# other.net
KiCad netlist of a schematic drawn in Altium Designer
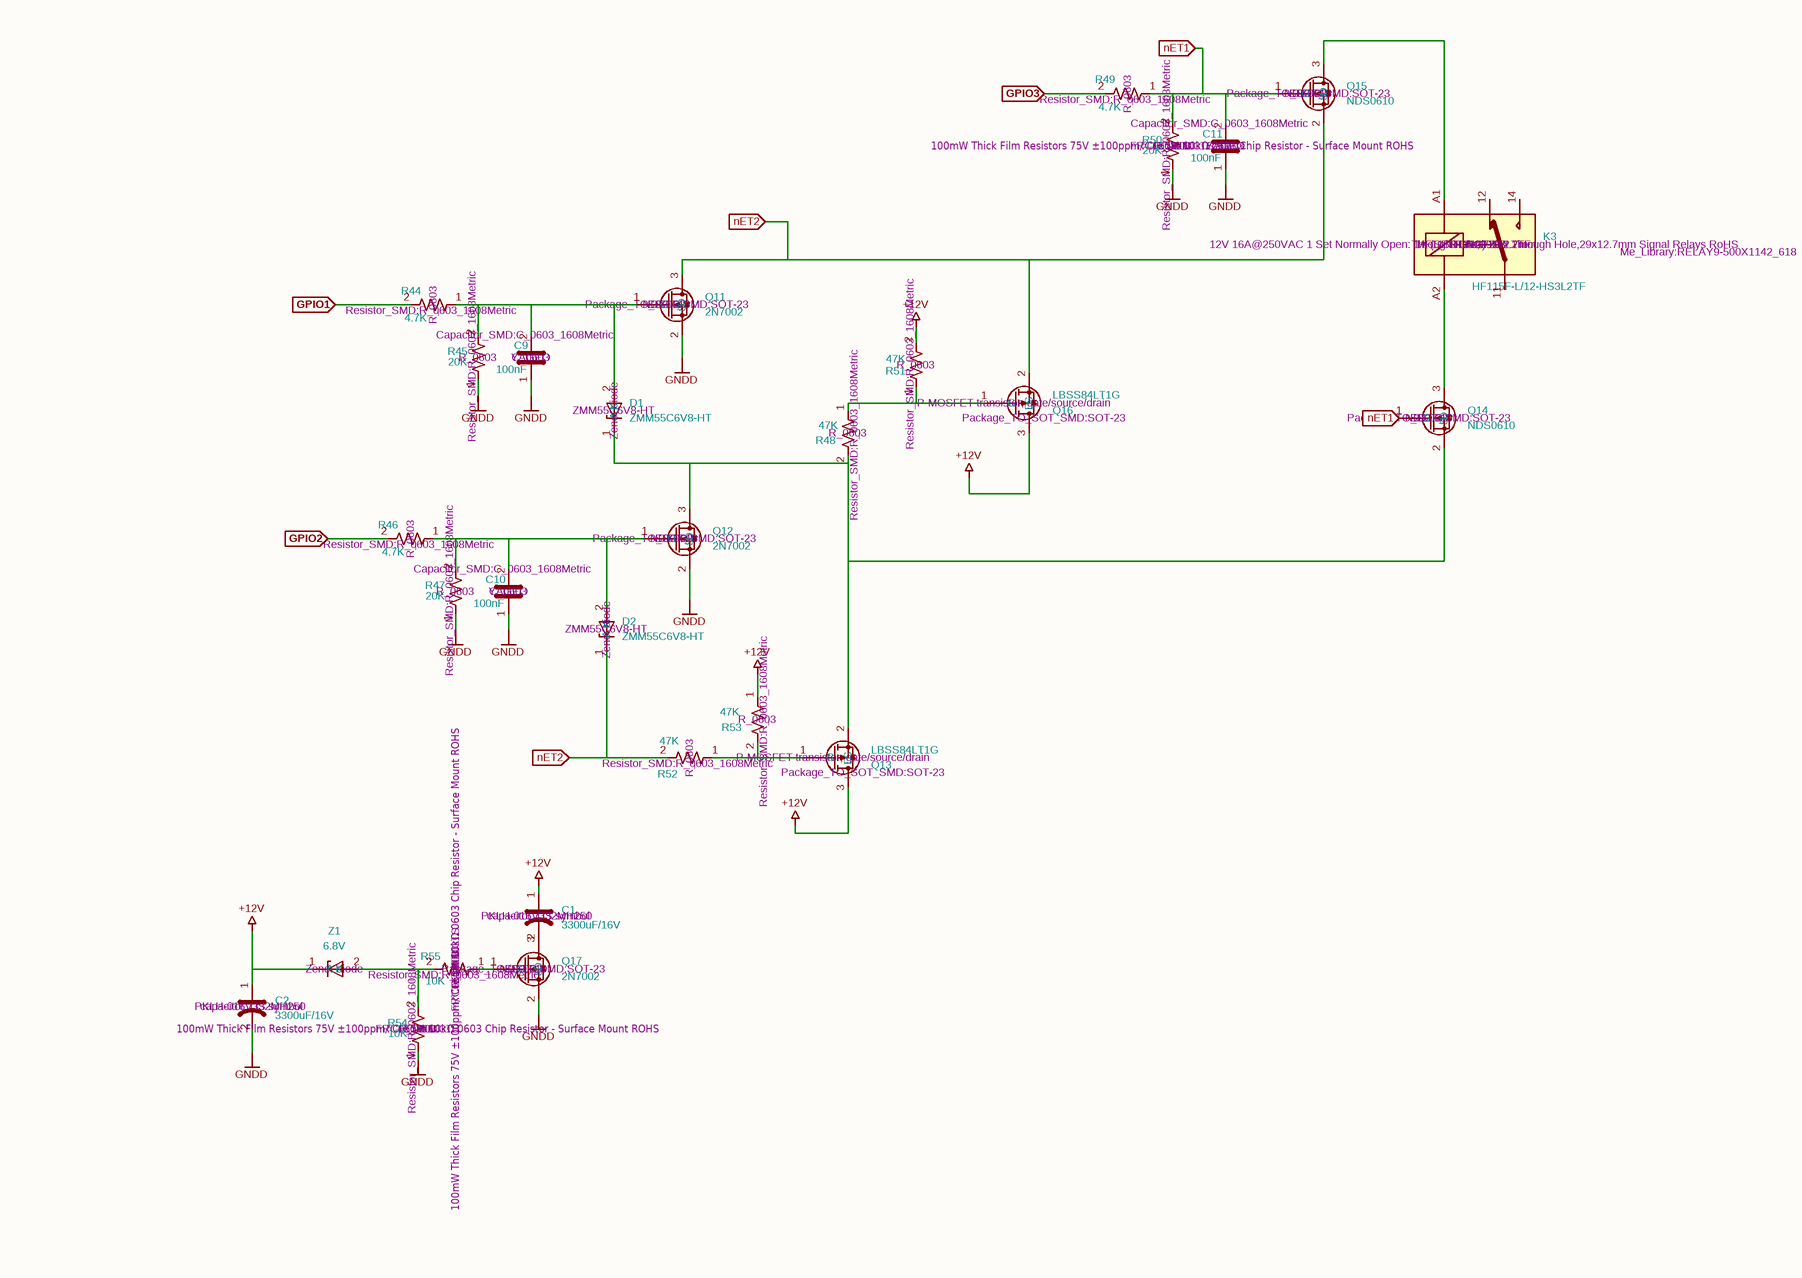
[diagram p0: other.SchDoc, left]
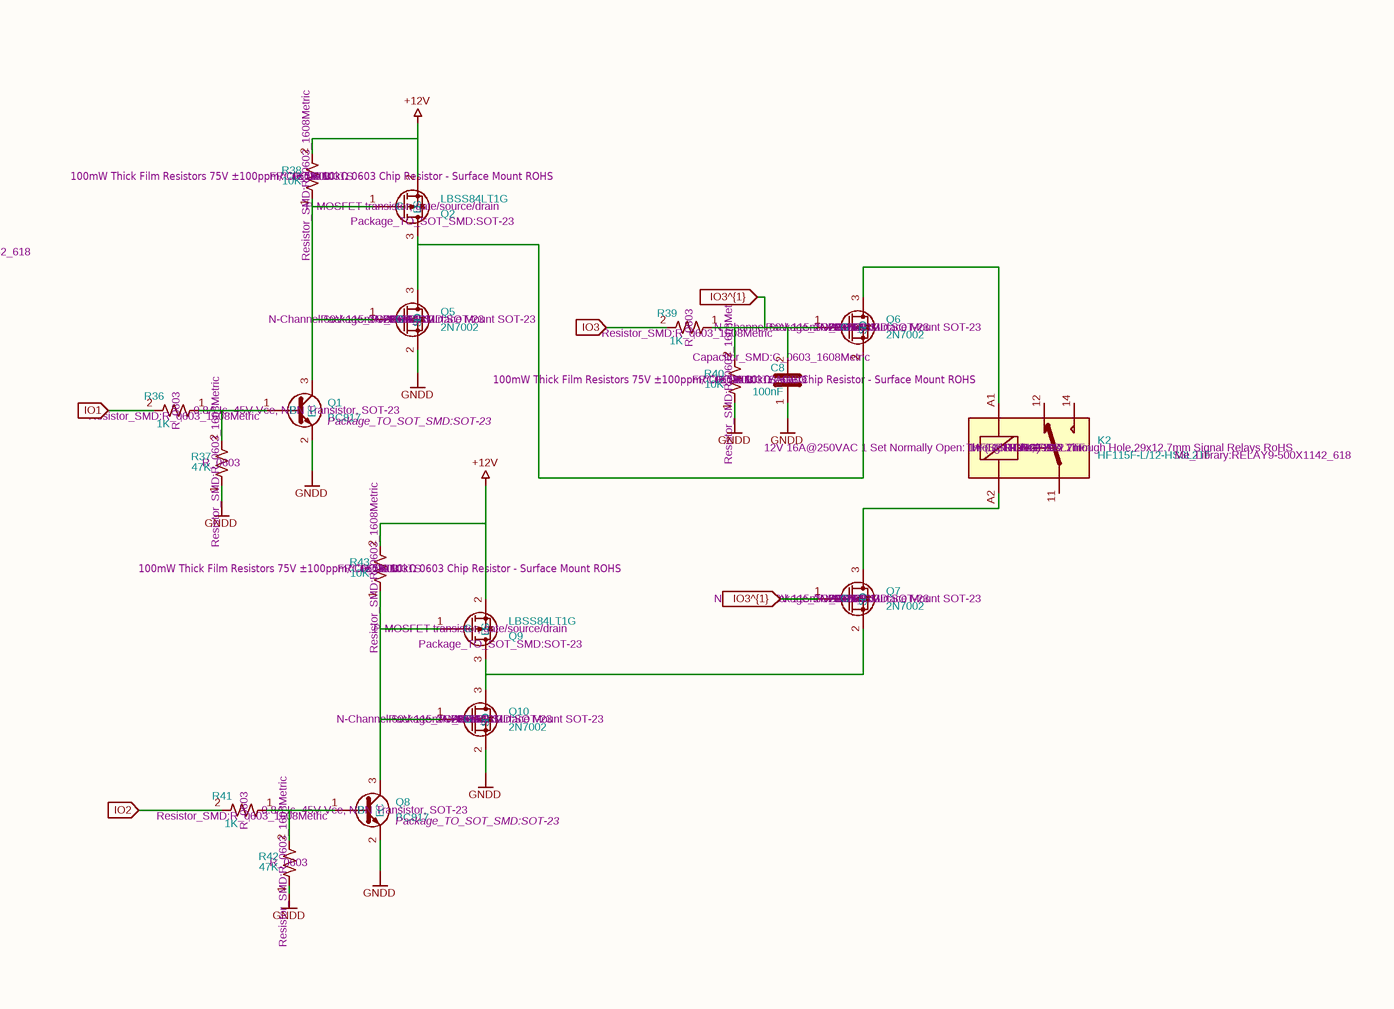
[diagram p1: other.SchDoc, right]

(export (version "E")
  (design (tool "Eeschema 10.0.6"))
  (components
    (comp (ref "C1")
      (value "3300uF/16V")
      (description "capacitor, US symbol")
      (fields (field (name "OZD") "PKLH-016V332MH250"))
      (libsource (lib "Device") (part "C_US"))
    )
    (comp (ref "C2")
      (value "3300uF/16V")
      (description "capacitor, US symbol")
      (fields (field (name "OZD") "PKLH-016V332MH250"))
      (libsource (lib "Device") (part "C_US"))
    )
    (comp (ref "C8")
      (value "100nF")
      (footprint "Capacitor_SMD:C_0603_1608Metric")
      (fields (field (name "MF") "YAGEO") (field (name "PACKAGE") "C_0603"))
      (libsource (lib "*") (part "C_3"))
    )
    (comp (ref "C9")
      (value "100nF")
      (footprint "Capacitor_SMD:C_0603_1608Metric")
      (fields (field (name "MF") "YAGEO") (field (name "PACKAGE") "C_0603"))
      (libsource (lib "*") (part "C_3"))
    )
    (comp (ref "C10")
      (value "100nF")
      (footprint "Capacitor_SMD:C_0603_1608Metric")
      (fields (field (name "MF") "YAGEO") (field (name "PACKAGE") "C_0603"))
      (libsource (lib "*") (part "C_3"))
    )
    (comp (ref "C11")
      (value "100nF")
      (footprint "Capacitor_SMD:C_0603_1608Metric")
      (fields (field (name "MF") "YAGEO") (field (name "PACKAGE") "C_0603"))
      (libsource (lib "*") (part "C_3"))
    )
    (comp (ref "D1")
      (value "ZMM55C6V8-HT")
      (description "Zener diode")
      (fields (field (name "OZD") "ZMM55C6V8-HT"))
      (libsource (lib "*") (part "D_Zener_1"))
    )
    (comp (ref "D2")
      (value "ZMM55C6V8-HT")
      (description "Zener diode")
      (fields (field (name "OZD") "ZMM55C6V8-HT"))
      (libsource (lib "Device") (part "D_Zener"))
    )
    (comp (ref "K2")
      (value "HF115F-L/12-HS3L2TF")
      (footprint "Me_Library:RELAY9-500X1142_618")
      (description "12V 16A@250VAC 1 Set Normally Open: 1A (SPST NO) 20A Through Hole,29x12.7mm Signal Relays RoHS")
      (fields
        (field (name "MP") "HF115F-L/12-HS3L2TF")
        (field (name "MF") "HONGFA")
        (field (name "PACKAGE") "Through Hole,29x12.7mm")
        (field (name "OZD") "RT314F12")
      )
      (libsource (lib "*") (part "RT314A03_1"))
    )
    (comp (ref "K3")
      (value "HF115F-L/12-HS3L2TF")
      (footprint "Me_Library:RELAY9-500X1142_618")
      (description "12V 16A@250VAC 1 Set Normally Open: 1A (SPST NO) 20A Through Hole,29x12.7mm Signal Relays RoHS")
      (fields
        (field (name "MP") "HF115F-L/12-HS3L2TF")
        (field (name "MF") "HONGFA")
        (field (name "PACKAGE") "Through Hole,29x12.7mm")
        (field (name "OZD") "RT314F12")
      )
      (libsource (lib "*") (part "RT314A03_1"))
    )
    (comp (ref "Q1")
      (value "BC817")
      (footprint "Package_TO_SOT_SMD:SOT-23")
      (description "0.8A Ic, 45V Vce, NPN Transistor, SOT-23")
      (libsource (lib "Transistor_BJT") (part "BC817"))
    )
    (comp (ref "Q2")
      (value "LBSS84LT1G")
      (footprint "Package_TO_SOT_SMD:SOT-23")
      (description "P-MOSFET transistor, gate/source/drain")
      (libsource (lib "Transistor_FET") (part "Q_PMOS_GSD"))
    )
    (comp (ref "Q5")
      (value "2N7002")
      (footprint "Package_TO_SOT_SMD:SOT-23")
      (description "N-Channel 60V 115mA 225mW Surface Mount SOT-23")
      (fields
        (field (name "MP") "2N7002")
        (field (name "MF") "FOSAN")
        (field (name "PACKAGE") "SOT-23")
        (field (name "OZD") "2N7002ET1G")
      )
      (libsource (lib "Transistor_FET_Other") (part "Q_NMOS_Depletion_GSD"))
    )
    (comp (ref "Q6")
      (value "2N7002")
      (footprint "Package_TO_SOT_SMD:SOT-23")
      (description "N-Channel 60V 115mA 225mW Surface Mount SOT-23")
      (fields
        (field (name "MP") "2N7002")
        (field (name "MF") "FOSAN")
        (field (name "PACKAGE") "SOT-23")
        (field (name "OZD") "2N7002ET1G")
      )
      (libsource (lib "Transistor_FET_Other") (part "Q_NMOS_Depletion_GSD"))
    )
    (comp (ref "Q7")
      (value "2N7002")
      (footprint "Package_TO_SOT_SMD:SOT-23")
      (description "N-Channel 60V 115mA 225mW Surface Mount SOT-23")
      (fields
        (field (name "MP") "2N7002")
        (field (name "MF") "FOSAN")
        (field (name "PACKAGE") "SOT-23")
        (field (name "OZD") "2N7002ET1G")
      )
      (libsource (lib "Transistor_FET_Other") (part "Q_NMOS_Depletion_GSD"))
    )
    (comp (ref "Q8")
      (value "BC817")
      (footprint "Package_TO_SOT_SMD:SOT-23")
      (description "0.8A Ic, 45V Vce, NPN Transistor, SOT-23")
      (libsource (lib "Transistor_BJT") (part "BC817"))
    )
    (comp (ref "Q9")
      (value "LBSS84LT1G")
      (footprint "Package_TO_SOT_SMD:SOT-23")
      (description "P-MOSFET transistor, gate/source/drain")
      (libsource (lib "Transistor_FET") (part "Q_PMOS_GSD"))
    )
    (comp (ref "Q10")
      (value "2N7002")
      (footprint "Package_TO_SOT_SMD:SOT-23")
      (description "N-Channel 60V 115mA 225mW Surface Mount SOT-23")
      (fields
        (field (name "MP") "2N7002")
        (field (name "MF") "FOSAN")
        (field (name "PACKAGE") "SOT-23")
        (field (name "OZD") "2N7002ET1G")
      )
      (libsource (lib "Transistor_FET_Other") (part "Q_NMOS_Depletion_GSD"))
    )
    (comp (ref "Q11")
      (value "2N7002")
      (footprint "Package_TO_SOT_SMD:SOT-23")
      (fields (field (name "MP") "NDS0610") (field (name "PACKAGE") "SOT-23"))
      (libsource (lib "Transistor_FET_Other") (part "Q_NMOS_Depletion_GSD"))
    )
    (comp (ref "Q12")
      (value "2N7002")
      (footprint "Package_TO_SOT_SMD:SOT-23")
      (fields (field (name "MP") "NDS0610") (field (name "PACKAGE") "SOT-23"))
      (libsource (lib "Transistor_FET_Other") (part "Q_NMOS_Depletion_GSD"))
    )
    (comp (ref "Q13")
      (value "LBSS84LT1G")
      (footprint "Package_TO_SOT_SMD:SOT-23")
      (description "P-MOSFET transistor, gate/source/drain")
      (libsource (lib "Transistor_FET") (part "Q_PMOS_GSD"))
    )
    (comp (ref "Q14")
      (value "NDS0610")
      (footprint "Package_TO_SOT_SMD:SOT-23")
      (fields (field (name "MP") "NDS0610") (field (name "PACKAGE") "SOT-23"))
      (libsource (lib "Transistor_FET_Other") (part "Q_NMOS_Depletion_GSD"))
    )
    (comp (ref "Q15")
      (value "NDS0610")
      (footprint "Package_TO_SOT_SMD:SOT-23")
      (fields (field (name "MP") "NDS0610") (field (name "PACKAGE") "SOT-23"))
      (libsource (lib "Transistor_FET_Other") (part "Q_NMOS_Depletion_GSD"))
    )
    (comp (ref "Q16")
      (value "LBSS84LT1G")
      (footprint "Package_TO_SOT_SMD:SOT-23")
      (description "P-MOSFET transistor, gate/source/drain")
      (libsource (lib "*") (part "Q_PMOS_GSD_1"))
    )
    (comp (ref "Q17")
      (value "2N7002")
      (footprint "Package_TO_SOT_SMD:SOT-23")
      (fields (field (name "MP") "NDS0610") (field (name "PACKAGE") "SOT-23"))
      (libsource (lib "Transistor_FET_Other") (part "Q_NMOS_Depletion_GSD"))
    )
    (comp (ref "R36")
      (value "1K")
      (footprint "Resistor_SMD:R_0603_1608Metric")
      (fields (field (name "PACKAGE") "R_0603"))
      (libsource (lib "Device") (part "R_US"))
    )
    (comp (ref "R37")
      (value "47K")
      (footprint "Resistor_SMD:R_0603_1608Metric")
      (fields (field (name "PACKAGE") "R_0603"))
      (libsource (lib "Device") (part "R_US"))
    )
    (comp (ref "R38")
      (value "10K")
      (footprint "Resistor_SMD:R_0603_1608Metric")
      (description "100mW Thick Film Resistors 75V ±100ppm/℃ ±5% 10kΩ 0603 Chip Resistor - Surface Mount ROHS")
      (fields
        (field (name "MP") "FRC0603J103TS")
        (field (name "MF") "FOJAN")
        (field (name "PACKAGE") "R_0603")
      )
      (libsource (lib "Device") (part "R_US"))
    )
    (comp (ref "R39")
      (value "1K")
      (footprint "Resistor_SMD:R_0603_1608Metric")
      (fields (field (name "PACKAGE") "R_0603"))
      (libsource (lib "Device") (part "R_US"))
    )
    (comp (ref "R40")
      (value "10K")
      (footprint "Resistor_SMD:R_0603_1608Metric")
      (description "100mW Thick Film Resistors 75V ±100ppm/℃ ±5% 10kΩ 0603 Chip Resistor - Surface Mount ROHS")
      (fields
        (field (name "MP") "FRC0603J103TS")
        (field (name "MF") "FOJAN")
        (field (name "PACKAGE") "R_0603")
      )
      (libsource (lib "Device") (part "R_US"))
    )
    (comp (ref "R41")
      (value "1K")
      (footprint "Resistor_SMD:R_0603_1608Metric")
      (fields (field (name "PACKAGE") "R_0603"))
      (libsource (lib "Device") (part "R_US"))
    )
    (comp (ref "R42")
      (value "47K")
      (footprint "Resistor_SMD:R_0603_1608Metric")
      (fields (field (name "PACKAGE") "R_0603"))
      (libsource (lib "Device") (part "R_US"))
    )
    (comp (ref "R43")
      (value "10K")
      (footprint "Resistor_SMD:R_0603_1608Metric")
      (description "100mW Thick Film Resistors 75V ±100ppm/℃ ±5% 10kΩ 0603 Chip Resistor - Surface Mount ROHS")
      (fields
        (field (name "MP") "FRC0603J103TS")
        (field (name "MF") "FOJAN")
        (field (name "PACKAGE") "R_0603")
      )
      (libsource (lib "Device") (part "R_US"))
    )
    (comp (ref "R44")
      (value "4.7K")
      (footprint "Resistor_SMD:R_0603_1608Metric")
      (fields (field (name "PACKAGE") "R_0603"))
      (libsource (lib "Device") (part "R_US"))
    )
    (comp (ref "R45")
      (value "20K")
      (footprint "Resistor_SMD:R_0603_1608Metric")
      (fields (field (name "PACKAGE") "R_0603"))
      (libsource (lib "Device") (part "R_US"))
    )
    (comp (ref "R46")
      (value "4.7K")
      (footprint "Resistor_SMD:R_0603_1608Metric")
      (fields (field (name "PACKAGE") "R_0603"))
      (libsource (lib "Device") (part "R_US"))
    )
    (comp (ref "R47")
      (value "20K")
      (footprint "Resistor_SMD:R_0603_1608Metric")
      (fields (field (name "PACKAGE") "R_0603"))
      (libsource (lib "Device") (part "R_US"))
    )
    (comp (ref "R48")
      (value "47K")
      (footprint "Resistor_SMD:R_0603_1608Metric")
      (fields (field (name "PACKAGE") "R_0603"))
      (libsource (lib "Device") (part "R_US"))
    )
    (comp (ref "R49")
      (value "4.7K")
      (footprint "Resistor_SMD:R_0603_1608Metric")
      (fields (field (name "PACKAGE") "R_0603"))
      (libsource (lib "Device") (part "R_US"))
    )
    (comp (ref "R50")
      (value "20K")
      (footprint "Resistor_SMD:R_0603_1608Metric")
      (description "100mW Thick Film Resistors 75V ±100ppm/℃ ±5% 10kΩ 0603 Chip Resistor - Surface Mount ROHS")
      (fields
        (field (name "MP") "FRC0603J103TS")
        (field (name "MF") "FOJAN")
        (field (name "PACKAGE") "R_0603")
      )
      (libsource (lib "Device") (part "R_US"))
    )
    (comp (ref "R51")
      (value "47K")
      (footprint "Resistor_SMD:R_0603_1608Metric")
      (fields (field (name "PACKAGE") "R_0603"))
      (libsource (lib "Device") (part "R_US"))
    )
    (comp (ref "R52")
      (value "47K")
      (footprint "Resistor_SMD:R_0603_1608Metric")
      (fields (field (name "PACKAGE") "R_0603"))
      (libsource (lib "Device") (part "R_US"))
    )
    (comp (ref "R53")
      (value "47K")
      (footprint "Resistor_SMD:R_0603_1608Metric")
      (fields (field (name "PACKAGE") "R_0603"))
      (libsource (lib "Device") (part "R_US"))
    )
    (comp (ref "R54")
      (value "10K")
      (footprint "Resistor_SMD:R_0603_1608Metric")
      (description "100mW Thick Film Resistors 75V ±100ppm/℃ ±5% 10kΩ 0603 Chip Resistor - Surface Mount ROHS")
      (fields
        (field (name "MP") "FRC0603J103TS")
        (field (name "MF") "FOJAN")
        (field (name "PACKAGE") "R_0603")
      )
      (libsource (lib "Device") (part "R_US"))
    )
    (comp (ref "R55")
      (value "10K")
      (footprint "Resistor_SMD:R_0603_1608Metric")
      (description "100mW Thick Film Resistors 75V ±100ppm/℃ ±5% 10kΩ 0603 Chip Resistor - Surface Mount ROHS")
      (fields
        (field (name "MP") "FRC0603J103TS")
        (field (name "MF") "FOJAN")
        (field (name "PACKAGE") "R_0603")
      )
      (libsource (lib "Device") (part "R_US"))
    )
    (comp (ref "Z1") (value "6.8V") (description "Zener diode") (libsource (lib "Device") (part "D_Zener")))
  )
  (nets
    (net (code "1") (name "+12V") (class "Default")
      (node (ref "C1") (pin "1") (pinfunction "1_1") (pintype "passive"))
      (node (ref "C2") (pin "1") (pinfunction "1_1") (pintype "passive"))
      (node (ref "Q13") (pin "3") (pinfunction "D_3") (pintype "passive"))
      (node (ref "Q16") (pin "3") (pinfunction "D_3") (pintype "passive"))
      (node (ref "Q2") (pin "2") (pinfunction "S_2") (pintype "passive"))
      (node (ref "Q9") (pin "2") (pinfunction "S_2") (pintype "passive"))
      (node (ref "R38") (pin "2") (pinfunction "2_2") (pintype "passive"))
      (node (ref "R43") (pin "2") (pinfunction "2_2") (pintype "passive"))
      (node (ref "R51") (pin "2") (pinfunction "2_2") (pintype "passive"))
      (node (ref "R53") (pin "1") (pinfunction "1_1") (pintype "passive"))
      (node (ref "Z1") (pin "1") (pinfunction "K_1") (pintype "passive"))
    )
    (net (code "2") (name "/GPIO1") (class "Default")
      (node (ref "R44") (pin "2") (pinfunction "2_2") (pintype "passive"))
    )
    (net (code "3") (name "/GPIO2") (class "Default")
      (node (ref "R46") (pin "2") (pinfunction "2_2") (pintype "passive"))
    )
    (net (code "4") (name "/GPIO3") (class "Default")
      (node (ref "R49") (pin "2") (pinfunction "2_2") (pintype "passive"))
    )
    (net (code "5") (name "/IO1") (class "Default")
      (node (ref "R36") (pin "2") (pinfunction "2_2") (pintype "passive"))
    )
    (net (code "6") (name "/IO2") (class "Default")
      (node (ref "R41") (pin "2") (pinfunction "2_2") (pintype "passive"))
    )
    (net (code "7") (name "/IO3") (class "Default")
      (node (ref "R39") (pin "2") (pinfunction "2_2") (pintype "passive"))
    )
    (net (code "8") (name "/IO3^{1}") (class "Default")
      (node (ref "C8") (pin "2") (pinfunction "2_2") (pintype "passive"))
      (node (ref "Q6") (pin "1") (pinfunction "G_1") (pintype "passive"))
      (node (ref "Q7") (pin "1") (pinfunction "G_1") (pintype "passive"))
      (node (ref "R39") (pin "1") (pinfunction "1_1") (pintype "passive"))
      (node (ref "R40") (pin "2") (pinfunction "2_2") (pintype "passive"))
    )
    (net (code "9") (name "/nET1") (class "Default")
      (node (ref "C11") (pin "2") (pinfunction "2_2") (pintype "passive"))
      (node (ref "Q14") (pin "1") (pinfunction "G_1") (pintype "passive"))
      (node (ref "Q15") (pin "1") (pinfunction "G_1") (pintype "passive"))
      (node (ref "R49") (pin "1") (pinfunction "1_1") (pintype "passive"))
      (node (ref "R50") (pin "2") (pinfunction "2_2") (pintype "passive"))
    )
    (net (code "10") (name "/nET2") (class "Default")
      (node (ref "D2") (pin "1") (pinfunction "K_1") (pintype "passive"))
      (node (ref "Q11") (pin "3") (pinfunction "D_3") (pintype "passive"))
      (node (ref "Q15") (pin "2") (pinfunction "S_2") (pintype "passive"))
      (node (ref "Q16") (pin "2") (pinfunction "S_2") (pintype "passive"))
      (node (ref "R52") (pin "2") (pinfunction "2_2") (pintype "passive"))
    )
    (net (code "11") (name "GNDD") (class "Default")
      (node (ref "C10") (pin "1") (pinfunction "1_1") (pintype "passive"))
      (node (ref "C11") (pin "1") (pinfunction "1_1") (pintype "passive"))
      (node (ref "C2") (pin "2") (pinfunction "2_2") (pintype "passive"))
      (node (ref "C8") (pin "1") (pinfunction "1_1") (pintype "passive"))
      (node (ref "C9") (pin "1") (pinfunction "1_1") (pintype "passive"))
      (node (ref "Q1") (pin "2") (pinfunction "E_2") (pintype "passive"))
      (node (ref "Q10") (pin "2") (pinfunction "S_2") (pintype "passive"))
      (node (ref "Q11") (pin "2") (pinfunction "S_2") (pintype "passive"))
      (node (ref "Q12") (pin "2") (pinfunction "S_2") (pintype "passive"))
      (node (ref "Q17") (pin "2") (pinfunction "S_2") (pintype "passive"))
      (node (ref "Q5") (pin "2") (pinfunction "S_2") (pintype "passive"))
      (node (ref "Q8") (pin "2") (pinfunction "E_2") (pintype "passive"))
      (node (ref "R37") (pin "1") (pinfunction "1_1") (pintype "passive"))
      (node (ref "R40") (pin "1") (pinfunction "1_1") (pintype "passive"))
      (node (ref "R42") (pin "1") (pinfunction "1_1") (pintype "passive"))
      (node (ref "R45") (pin "1") (pinfunction "1_1") (pintype "passive"))
      (node (ref "R47") (pin "1") (pinfunction "1_1") (pintype "passive"))
      (node (ref "R50") (pin "1") (pinfunction "1_1") (pintype "passive"))
      (node (ref "R54") (pin "1") (pinfunction "1_1") (pintype "passive"))
    )
    (net (code "12") (name "Net-(D1-A)") (class "Default")
      (node (ref "C9") (pin "2") (pinfunction "2_2") (pintype "passive"))
      (node (ref "D1") (pin "2") (pinfunction "A_2") (pintype "passive"))
      (node (ref "Q11") (pin "1") (pinfunction "G_1") (pintype "passive"))
      (node (ref "R44") (pin "1") (pinfunction "1_1") (pintype "passive"))
      (node (ref "R45") (pin "2") (pinfunction "2_2") (pintype "passive"))
    )
    (net (code "13") (name "Net-(D1-K)") (class "Default")
      (node (ref "D1") (pin "1") (pinfunction "K_1") (pintype "passive"))
      (node (ref "Q12") (pin "3") (pinfunction "D_3") (pintype "passive"))
      (node (ref "Q13") (pin "2") (pinfunction "S_2") (pintype "passive"))
      (node (ref "Q14") (pin "2") (pinfunction "S_2") (pintype "passive"))
      (node (ref "R48") (pin "2") (pinfunction "2_2") (pintype "passive"))
    )
    (net (code "14") (name "Net-(D2-A)") (class "Default")
      (node (ref "C10") (pin "2") (pinfunction "2_2") (pintype "passive"))
      (node (ref "D2") (pin "2") (pinfunction "A_2") (pintype "passive"))
      (node (ref "Q12") (pin "1") (pinfunction "G_1") (pintype "passive"))
      (node (ref "R46") (pin "1") (pinfunction "1_1") (pintype "passive"))
      (node (ref "R47") (pin "2") (pinfunction "2_2") (pintype "passive"))
    )
    (net (code "15") (name "Net-(Q1-B)") (class "Default")
      (node (ref "Q1") (pin "1") (pinfunction "B_1") (pintype "passive"))
      (node (ref "R36") (pin "1") (pinfunction "1_1") (pintype "passive"))
      (node (ref "R37") (pin "2") (pinfunction "2_2") (pintype "passive"))
    )
    (net (code "16") (name "Net-(Q1-C)") (class "Default")
      (node (ref "Q1") (pin "3") (pinfunction "C_3") (pintype "passive"))
      (node (ref "Q2") (pin "1") (pinfunction "G_1") (pintype "passive"))
      (node (ref "Q5") (pin "1") (pinfunction "G_1") (pintype "passive"))
      (node (ref "R38") (pin "1") (pinfunction "1_1") (pintype "passive"))
    )
    (net (code "17") (name "Net-(Q2-D)") (class "Default")
      (node (ref "Q2") (pin "3") (pinfunction "D_3") (pintype "passive"))
      (node (ref "Q5") (pin "3") (pinfunction "D_3") (pintype "passive"))
      (node (ref "Q6") (pin "2") (pinfunction "S_2") (pintype "passive"))
    )
    (net (code "18") (name "Net-(Q6-D)") (class "Default")
      (node (ref "K2") (pin "A1") (pinfunction "A1_A1") (pintype "passive"))
      (node (ref "Q6") (pin "3") (pinfunction "D_3") (pintype "passive"))
    )
    (net (code "19") (name "Net-(Q7-D)") (class "Default")
      (node (ref "K2") (pin "A2") (pinfunction "A2_A2") (pintype "passive"))
      (node (ref "Q7") (pin "3") (pinfunction "D_3") (pintype "passive"))
    )
    (net (code "20") (name "Net-(Q8-B)") (class "Default")
      (node (ref "Q8") (pin "1") (pinfunction "B_1") (pintype "passive"))
      (node (ref "R41") (pin "1") (pinfunction "1_1") (pintype "passive"))
      (node (ref "R42") (pin "2") (pinfunction "2_2") (pintype "passive"))
    )
    (net (code "21") (name "Net-(Q10-D)") (class "Default")
      (node (ref "Q10") (pin "3") (pinfunction "D_3") (pintype "passive"))
      (node (ref "Q7") (pin "2") (pinfunction "S_2") (pintype "passive"))
      (node (ref "Q9") (pin "3") (pinfunction "D_3") (pintype "passive"))
    )
    (net (code "22") (name "Net-(Q10-G)") (class "Default")
      (node (ref "Q10") (pin "1") (pinfunction "G_1") (pintype "passive"))
      (node (ref "Q8") (pin "3") (pinfunction "C_3") (pintype "passive"))
      (node (ref "Q9") (pin "1") (pinfunction "G_1") (pintype "passive"))
      (node (ref "R43") (pin "1") (pinfunction "1_1") (pintype "passive"))
    )
    (net (code "23") (name "Net-(Q13-G)") (class "Default")
      (node (ref "Q13") (pin "1") (pinfunction "G_1") (pintype "passive"))
      (node (ref "R52") (pin "1") (pinfunction "1_1") (pintype "passive"))
      (node (ref "R53") (pin "2") (pinfunction "2_2") (pintype "passive"))
    )
    (net (code "24") (name "Net-(Q14-D)") (class "Default")
      (node (ref "K3") (pin "A2") (pinfunction "A2_A2") (pintype "passive"))
      (node (ref "Q14") (pin "3") (pinfunction "D_3") (pintype "passive"))
    )
    (net (code "25") (name "Net-(Q15-D)") (class "Default")
      (node (ref "K3") (pin "A1") (pinfunction "A1_A1") (pintype "passive"))
      (node (ref "Q15") (pin "3") (pinfunction "D_3") (pintype "passive"))
    )
    (net (code "26") (name "Net-(Q16-G)") (class "Default")
      (node (ref "Q16") (pin "1") (pinfunction "G_1") (pintype "passive"))
      (node (ref "R48") (pin "1") (pinfunction "1_1") (pintype "passive"))
      (node (ref "R51") (pin "1") (pinfunction "1_1") (pintype "passive"))
    )
    (net (code "27") (name "Net-(Q17-D)") (class "Default")
      (node (ref "C1") (pin "2") (pinfunction "2_2") (pintype "passive"))
      (node (ref "Q17") (pin "3") (pinfunction "D_3") (pintype "passive"))
    )
    (net (code "28") (name "Net-(Q17-G)") (class "Default")
      (node (ref "Q17") (pin "1") (pinfunction "G_1") (pintype "passive"))
      (node (ref "R55") (pin "1") (pinfunction "1_1") (pintype "passive"))
    )
    (net (code "29") (name "Net-(Z1-A)") (class "Default")
      (node (ref "R54") (pin "2") (pinfunction "2_2") (pintype "passive"))
      (node (ref "R55") (pin "2") (pinfunction "2_2") (pintype "passive"))
      (node (ref "Z1") (pin "2") (pinfunction "A_2") (pintype "passive"))
    )
    (net (code "30") (name "unconnected-(K2-Pad11)") (class "Default")
      (node (ref "K2") (pin "11") (pinfunction "11_11") (pintype "passive"))
    )
    (net (code "31") (name "unconnected-(K2-Pad12)") (class "Default")
      (node (ref "K2") (pin "12") (pinfunction "12_12") (pintype "passive"))
    )
    (net (code "32") (name "unconnected-(K2-Pad14)") (class "Default")
      (node (ref "K2") (pin "14") (pinfunction "14_14") (pintype "passive"))
    )
    (net (code "33") (name "unconnected-(K3-Pad11)") (class "Default")
      (node (ref "K3") (pin "11") (pinfunction "11_11") (pintype "passive"))
    )
    (net (code "34") (name "unconnected-(K3-Pad12)") (class "Default")
      (node (ref "K3") (pin "12") (pinfunction "12_12") (pintype "passive"))
    )
    (net (code "35") (name "unconnected-(K3-Pad14)") (class "Default")
      (node (ref "K3") (pin "14") (pinfunction "14_14") (pintype "passive"))
    )
  )
)
